# battery_controller.net
KiCad netlist of a schematic drawn in EAGLE
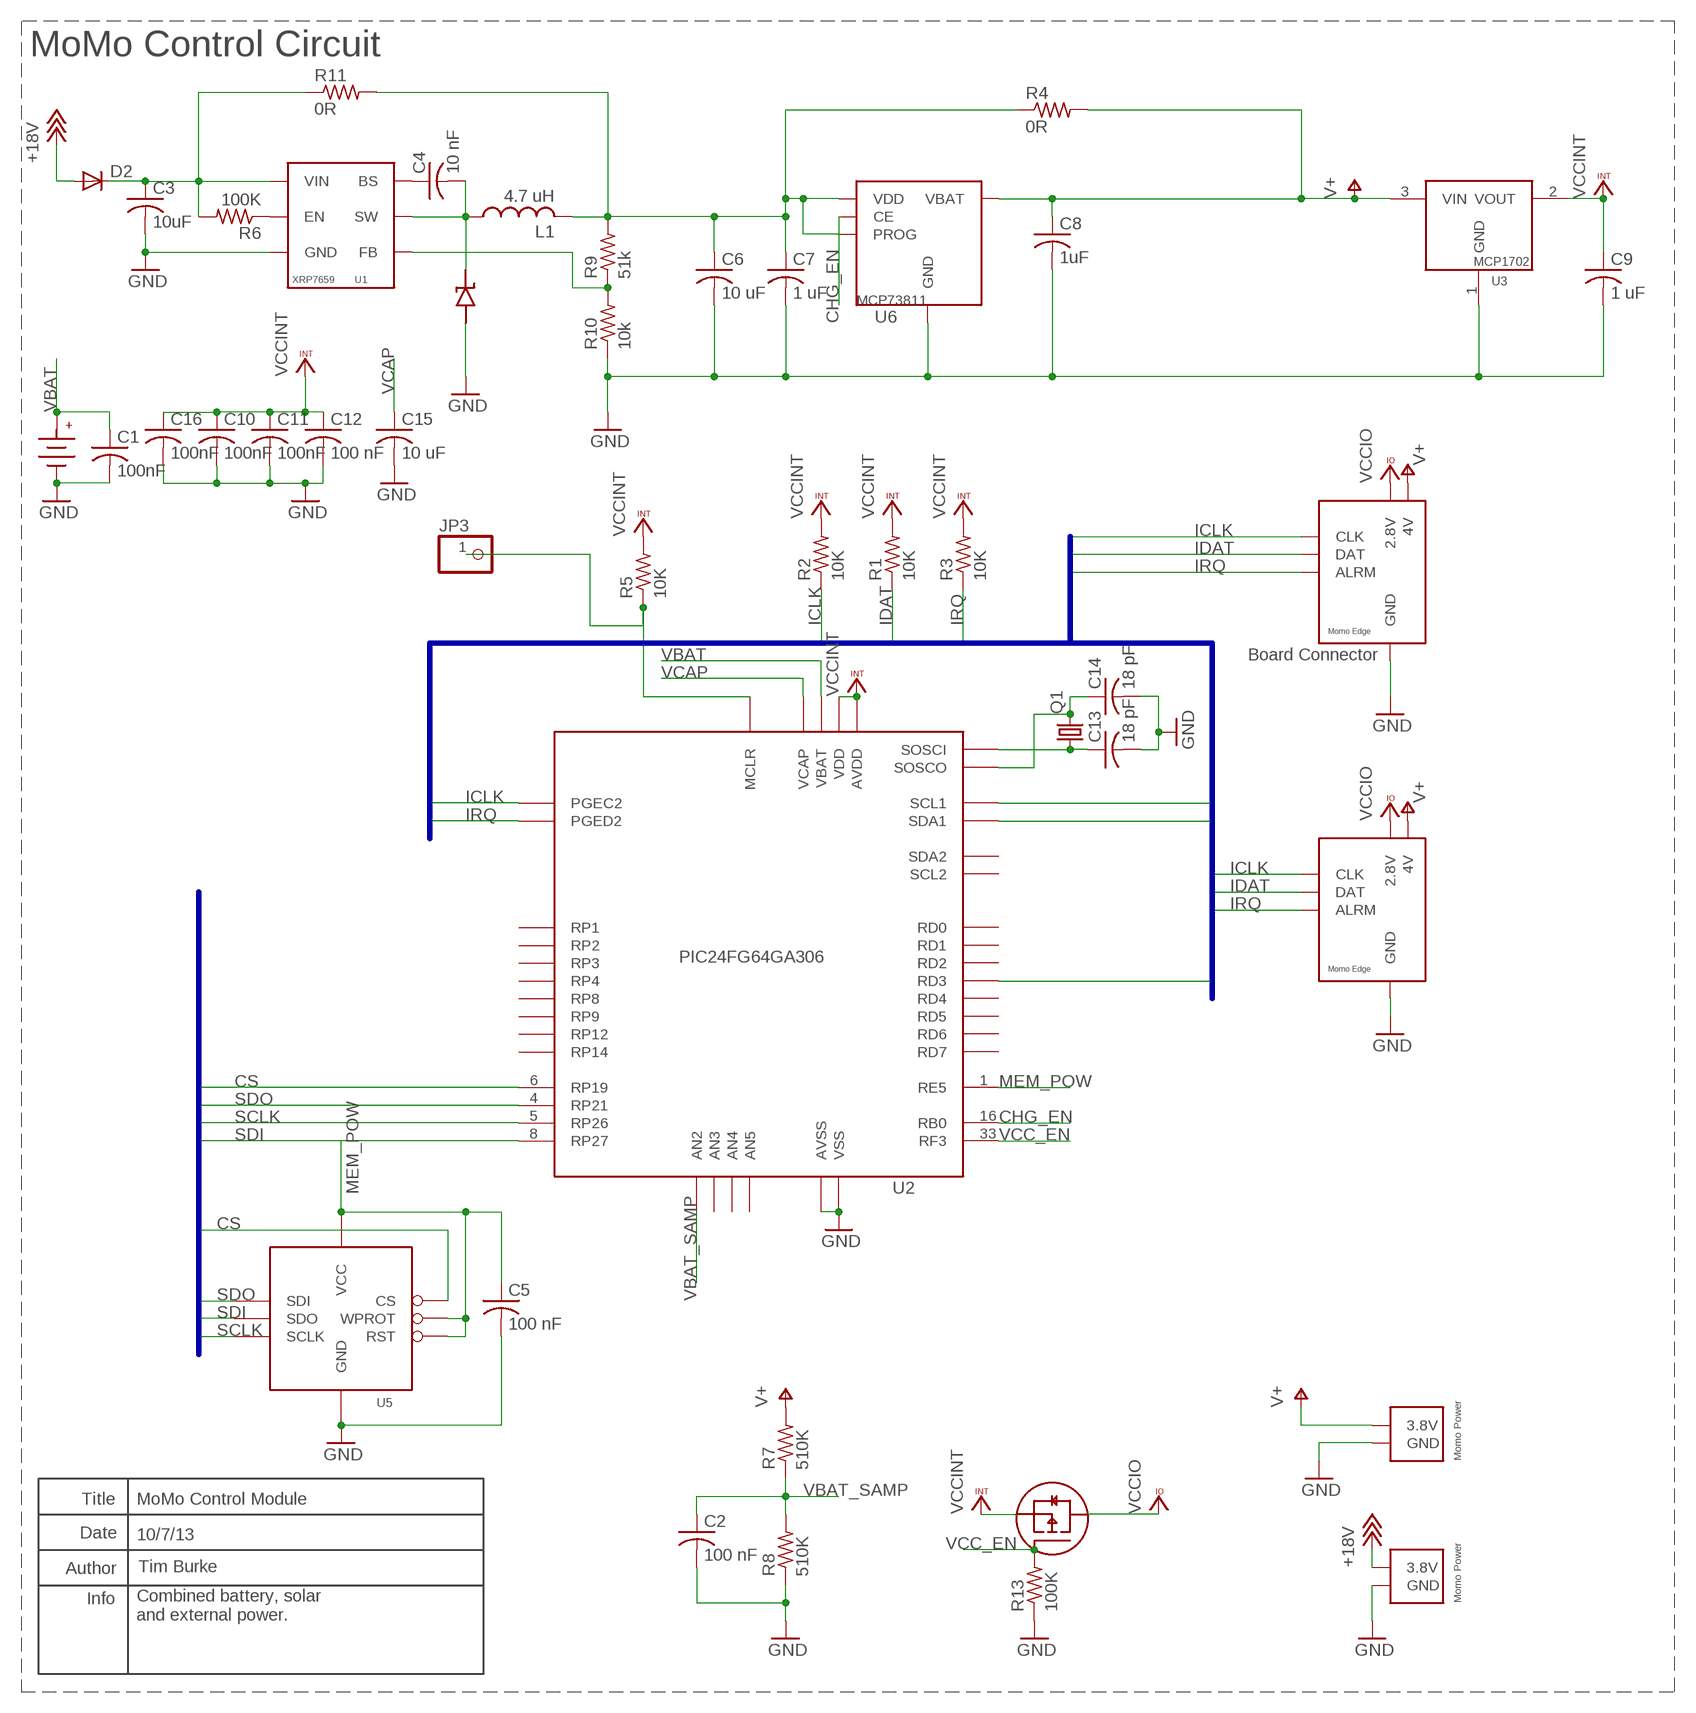
[diagram p0: schematic, sheet 1]

(export (version "E")
  (design (tool "Eeschema 10.0.6"))
  (components
    (comp (ref "BATT1")
      (value "CR1025-HOLDER")
      (footprint "eagle-import:CR1025-HOLDER")
      (libsource (lib "eagle-import") (part "CR1025-HOLDER"))
    )
    (comp (ref "C1")
      (value "100nF")
      (footprint "eagle-import:C0402")
      (libsource (lib "eagle-import") (part "C-USC0402"))
    )
    (comp (ref "C2")
      (value "100 nF")
      (footprint "eagle-import:C0402")
      (libsource (lib "eagle-import") (part "C-USC0402"))
    )
    (comp (ref "C3")
      (value "10uF")
      (footprint "eagle-import:C0805")
      (libsource (lib "eagle-import") (part "C-USC0805"))
    )
    (comp (ref "C4")
      (value "10 nF")
      (footprint "eagle-import:C0402")
      (libsource (lib "eagle-import") (part "C-USC0402"))
    )
    (comp (ref "C5")
      (value "100 nF")
      (footprint "eagle-import:C0402")
      (libsource (lib "eagle-import") (part "C-USC0402"))
    )
    (comp (ref "C6")
      (value "10 uF")
      (footprint "eagle-import:C0805")
      (libsource (lib "eagle-import") (part "C-USC0805"))
    )
    (comp (ref "C7")
      (value "1 uF")
      (footprint "eagle-import:C0402")
      (libsource (lib "eagle-import") (part "C-USC0402"))
    )
    (comp (ref "C8")
      (value "1uF")
      (footprint "eagle-import:C0402")
      (libsource (lib "eagle-import") (part "C-USC0402"))
    )
    (comp (ref "C9")
      (value "1 uF")
      (footprint "eagle-import:C0402")
      (libsource (lib "eagle-import") (part "C-USC0402"))
    )
    (comp (ref "C10")
      (value "100nF")
      (footprint "eagle-import:C0402")
      (libsource (lib "eagle-import") (part "C-USC0402"))
    )
    (comp (ref "C11")
      (value "100nF")
      (footprint "eagle-import:C0402")
      (libsource (lib "eagle-import") (part "C-USC0402"))
    )
    (comp (ref "C12")
      (value "100 nF")
      (footprint "eagle-import:C0402")
      (libsource (lib "eagle-import") (part "C-USC0402"))
    )
    (comp (ref "C13")
      (value "18 pF")
      (footprint "eagle-import:C0402K")
      (libsource (lib "eagle-import") (part "C-USC0402K"))
    )
    (comp (ref "C14")
      (value "18 pF")
      (footprint "eagle-import:C0402K")
      (libsource (lib "eagle-import") (part "C-USC0402K"))
    )
    (comp (ref "C15")
      (value "10 uF")
      (footprint "eagle-import:C0805")
      (libsource (lib "eagle-import") (part "C-USC0805"))
    )
    (comp (ref "C16")
      (value "100nF")
      (footprint "eagle-import:C0402")
      (libsource (lib "eagle-import") (part "C-USC0402"))
    )
    (comp (ref "D1")
      (value "DIODE_SS2P3SS2P3")
      (footprint "eagle-import:DIODE_SS2P3")
      (libsource (lib "eagle-import") (part "DIODE_SS2P3SS2P3"))
    )
    (comp (ref "D2")
      (value "DIODE-DO214AC")
      (footprint "eagle-import:DO214AC")
      (description "Schottky Diode")
      (libsource (lib "eagle-import") (part "DIODE-DO214AC"))
    )
    (comp (ref "JP1")
      (value "MOMO-VERT-6M")
      (footprint "eagle-import:1X06")
      (libsource (lib "eagle-import") (part "MOMO-VERT-6M"))
    )
    (comp (ref "JP2")
      (value "MOMO-EDGE-6F")
      (footprint "eagle-import:MOMO-EDGE-8F")
      (libsource (lib "eagle-import") (part "MOMO-EDGE-6F"))
    )
    (comp (ref "JP3")
      (value "PINHD-1X1")
      (footprint "eagle-import:1X01")
      (libsource (lib "eagle-import") (part "PINHD-1X1"))
    )
    (comp (ref "JP4")
      (value "MOMO-EDGE-POWER-M")
      (footprint "eagle-import:MOMO-EDGE-SMALL-2M")
      (fields (field (name "DIGIKEY-PN") "A19450-ND"))
      (libsource (lib "eagle-import") (part "MOMO-EDGE-POWER-M"))
    )
    (comp (ref "JP5")
      (value "MOMO-EDGE-POWER-M")
      (footprint "eagle-import:MOMO-EDGE-SMALL-2M")
      (fields (field (name "DIGIKEY-PN") "A19450-ND"))
      (libsource (lib "eagle-import") (part "MOMO-EDGE-POWER-M"))
    )
    (comp (ref "L1")
      (value "4.7 uH")
      (footprint "eagle-import:NR6028-INDUCTOR")
      (libsource (lib "eagle-import") (part "NR6028-INDUCTOR"))
    )
    (comp (ref "Q1")
      (value "CRYSTALTC26H")
      (footprint "eagle-import:TC26H")
      (libsource (lib "eagle-import") (part "CRYSTALTC26H"))
    )
    (comp (ref "Q2")
      (value "P-MOSFET")
      (footprint "eagle-import:SOT23")
      (libsource (lib "eagle-import") (part "P-MOSFET"))
    )
    (comp (ref "R1")
      (value "10K")
      (footprint "eagle-import:R0603")
      (libsource (lib "eagle-import") (part "R-US_R0603"))
    )
    (comp (ref "R2")
      (value "10K")
      (footprint "eagle-import:R0603")
      (libsource (lib "eagle-import") (part "R-US_R0603"))
    )
    (comp (ref "R3")
      (value "10K")
      (footprint "eagle-import:R0603")
      (libsource (lib "eagle-import") (part "R-US_R0603"))
    )
    (comp (ref "R4")
      (value "0R")
      (footprint "eagle-import:R0603")
      (libsource (lib "eagle-import") (part "R-US_R0603"))
    )
    (comp (ref "R5")
      (value "10K")
      (footprint "eagle-import:R0603")
      (libsource (lib "eagle-import") (part "R-US_R0603"))
    )
    (comp (ref "R6")
      (value "100K")
      (footprint "eagle-import:R0603")
      (libsource (lib "eagle-import") (part "R-US_R0603"))
    )
    (comp (ref "R7")
      (value "510K")
      (footprint "eagle-import:R0603")
      (libsource (lib "eagle-import") (part "R-US_R0603"))
    )
    (comp (ref "R8")
      (value "510K")
      (footprint "eagle-import:R0603")
      (libsource (lib "eagle-import") (part "R-US_R0603"))
    )
    (comp (ref "R9")
      (value "51k")
      (footprint "eagle-import:R0603")
      (libsource (lib "eagle-import") (part "R-US_R0603"))
    )
    (comp (ref "R10")
      (value "10k")
      (footprint "eagle-import:R0603")
      (libsource (lib "eagle-import") (part "R-US_R0603"))
    )
    (comp (ref "R11")
      (value "0R")
      (footprint "eagle-import:R0603")
      (libsource (lib "eagle-import") (part "R-US_R0603"))
    )
    (comp (ref "R13")
      (value "100K")
      (footprint "eagle-import:R0603")
      (libsource (lib "eagle-import") (part "R-US_R0603"))
    )
    (comp (ref "U1")
      (value "XRP7659")
      (footprint "eagle-import:SOT23-6L")
      (libsource (lib "eagle-import") (part "XRP7659"))
    )
    (comp (ref "U2")
      (value "PIC24FJ64GA306")
      (footprint "eagle-import:TQFP64-10X10")
      (libsource (lib "eagle-import") (part "PIC24FJ64GA306"))
    )
    (comp (ref "U3")
      (value "MCP1702")
      (footprint "eagle-import:SOT23")
      (libsource (lib "eagle-import") (part "MCP1702"))
    )
    (comp (ref "U5")
      (value "FLASH8MSOP8")
      (footprint "eagle-import:SOP08")
      (libsource (lib "eagle-import") (part "FLASH8MSOP8"))
    )
    (comp (ref "U6")
      (value "MCP73811")
      (footprint "eagle-import:SOT23-5L")
      (libsource (lib "eagle-import") (part "MCP73811"))
    )
  )
  (nets
    (net (code "1") (name "+18V") (class "Default")
      (node (ref "D2") (pin "A") (pinfunction "A_A") (pintype "passive"))
      (node (ref "JP5") (pin "2") (pinfunction "3.8V_2") (pintype "power_in"))
    )
    (net (code "2") (name "/CHG_EN") (class "Default")
      (node (ref "U2") (pin "16") (pinfunction "RB0_16") (pintype "bidirectional"))
      (node (ref "U6") (pin "1") (pinfunction "CE_1") (pintype "bidirectional"))
    )
    (net (code "3") (name "/CS") (class "Default")
      (node (ref "U2") (pin "6") (pinfunction "RP19_6") (pintype "bidirectional"))
      (node (ref "U5") (pin "1") (pinfunction "CS_1") (pintype "bidirectional"))
    )
    (net (code "4") (name "/ICLK") (class "Default")
      (node (ref "JP1") (pin "3") (pinfunction "CLK_3") (pintype "bidirectional"))
      (node (ref "JP2") (pin "CLK") (pinfunction "CLK_CLK") (pintype "bidirectional"))
      (node (ref "R2") (pin "1") (pinfunction "1_1") (pintype "passive"))
      (node (ref "U2") (pin "17") (pinfunction "PGEC2_17") (pintype "bidirectional"))
      (node (ref "U2") (pin "37") (pinfunction "SCL1_37") (pintype "bidirectional"))
    )
    (net (code "5") (name "/IDAT") (class "Default")
      (node (ref "JP1") (pin "4") (pinfunction "DAT_4") (pintype "bidirectional"))
      (node (ref "JP2") (pin "DAT") (pinfunction "DAT_DAT") (pintype "bidirectional"))
      (node (ref "R1") (pin "1") (pinfunction "1_1") (pintype "passive"))
      (node (ref "U2") (pin "36") (pinfunction "SDA1_36") (pintype "bidirectional"))
    )
    (net (code "6") (name "/IRQ") (class "Default")
      (node (ref "JP1") (pin "5") (pinfunction "ALRM_5") (pintype "bidirectional"))
      (node (ref "JP2") (pin "ARLM") (pinfunction "ALRM_ARLM") (pintype "bidirectional"))
      (node (ref "R3") (pin "1") (pinfunction "1_1") (pintype "passive"))
      (node (ref "U2") (pin "18") (pinfunction "PGED2_18") (pintype "bidirectional"))
      (node (ref "U2") (pin "51") (pinfunction "RD3_51") (pintype "bidirectional"))
    )
    (net (code "7") (name "/MEM_POW") (class "Default")
      (node (ref "C5") (pin "1") (pinfunction "1_1") (pintype "passive"))
      (node (ref "U2") (pin "1") (pinfunction "RE5_1") (pintype "bidirectional"))
      (node (ref "U5") (pin "3") (pinfunction "WPROT_3") (pintype "bidirectional"))
      (node (ref "U5") (pin "7") (pinfunction "RST_7") (pintype "bidirectional"))
      (node (ref "U5") (pin "8") (pinfunction "VCC_8") (pintype "power_in"))
    )
    (net (code "8") (name "/SCLK") (class "Default")
      (node (ref "U2") (pin "5") (pinfunction "RP26_5") (pintype "bidirectional"))
      (node (ref "U5") (pin "6") (pinfunction "SCLK_6") (pintype "bidirectional"))
    )
    (net (code "9") (name "/SDI") (class "Default")
      (node (ref "U2") (pin "8") (pinfunction "RP27_8") (pintype "bidirectional"))
      (node (ref "U5") (pin "2") (pinfunction "SDO_2") (pintype "bidirectional"))
    )
    (net (code "10") (name "/SDO") (class "Default")
      (node (ref "U2") (pin "4") (pinfunction "RP21_4") (pintype "bidirectional"))
      (node (ref "U5") (pin "5") (pinfunction "SDI_5") (pintype "bidirectional"))
    )
    (net (code "11") (name "/VBAT") (class "Default")
      (node (ref "BATT1") (pin "+") (pinfunction "+_+") (pintype "power_in"))
      (node (ref "C1") (pin "1") (pinfunction "1_1") (pintype "passive"))
      (node (ref "U2") (pin "57") (pinfunction "VBAT_57") (pintype "bidirectional"))
    )
    (net (code "12") (name "/VBAT_SAMP") (class "Default")
      (node (ref "C2") (pin "1") (pinfunction "1_1") (pintype "passive"))
      (node (ref "R7") (pin "1") (pinfunction "1_1") (pintype "passive"))
      (node (ref "R8") (pin "2") (pinfunction "2_2") (pintype "passive"))
      (node (ref "U2") (pin "14") (pinfunction "AN2_14") (pintype "bidirectional"))
    )
    (net (code "13") (name "/VCAP") (class "Default")
      (node (ref "C15") (pin "1") (pinfunction "1_1") (pintype "passive"))
      (node (ref "U2") (pin "56") (pinfunction "VCAP_56") (pintype "bidirectional"))
    )
    (net (code "14") (name "/VCC_EN") (class "Default")
      (node (ref "Q2") (pin "1") (pinfunction "GATE_1") (pintype "bidirectional"))
      (node (ref "R13") (pin "2") (pinfunction "2_2") (pintype "passive"))
      (node (ref "U2") (pin "33") (pinfunction "RF3_33") (pintype "bidirectional"))
    )
    (net (code "15") (name "GND") (class "Default")
      (node (ref "BATT1") (pin "-1") (pinfunction "-_-1") (pintype "power_in"))
      (node (ref "BATT1") (pin "-2") (pinfunction "-_-2") (pintype "power_in"))
      (node (ref "C1") (pin "2") (pinfunction "2_2") (pintype "passive"))
      (node (ref "C10") (pin "2") (pinfunction "2_2") (pintype "passive"))
      (node (ref "C11") (pin "2") (pinfunction "2_2") (pintype "passive"))
      (node (ref "C12") (pin "2") (pinfunction "2_2") (pintype "passive"))
      (node (ref "C13") (pin "2") (pinfunction "2_2") (pintype "passive"))
      (node (ref "C14") (pin "2") (pinfunction "2_2") (pintype "passive"))
      (node (ref "C15") (pin "2") (pinfunction "2_2") (pintype "passive"))
      (node (ref "C16") (pin "2") (pinfunction "2_2") (pintype "passive"))
      (node (ref "C2") (pin "2") (pinfunction "2_2") (pintype "passive"))
      (node (ref "C3") (pin "2") (pinfunction "2_2") (pintype "passive"))
      (node (ref "C5") (pin "2") (pinfunction "2_2") (pintype "passive"))
      (node (ref "C6") (pin "2") (pinfunction "2_2") (pintype "passive"))
      (node (ref "C7") (pin "2") (pinfunction "2_2") (pintype "passive"))
      (node (ref "C8") (pin "2") (pinfunction "2_2") (pintype "passive"))
      (node (ref "C9") (pin "2") (pinfunction "2_2") (pintype "passive"))
      (node (ref "D1") (pin "AN") (pinfunction "AN_AN") (pintype "bidirectional"))
      (node (ref "JP1") (pin "7") (pinfunction "GND_7") (pintype "power_in"))
      (node (ref "JP2") (pin "GND") (pinfunction "GND_GND") (pintype "power_in"))
      (node (ref "JP4") (pin "1") (pinfunction "GND_1") (pintype "power_in"))
      (node (ref "JP5") (pin "1") (pinfunction "GND_1") (pintype "power_in"))
      (node (ref "R10") (pin "1") (pinfunction "1_1") (pintype "passive"))
      (node (ref "R13") (pin "1") (pinfunction "1_1") (pintype "passive"))
      (node (ref "R8") (pin "1") (pinfunction "1_1") (pintype "passive"))
      (node (ref "U1") (pin "2") (pinfunction "GND_2") (pintype "bidirectional"))
      (node (ref "U2") (pin "20") (pinfunction "AVSS_20") (pintype "bidirectional"))
      (node (ref "U2") (pin "25") (pinfunction "VSS_25") (pintype "bidirectional"))
      (node (ref "U2") (pin "41") (pinfunction "VSS_41") (pintype "bidirectional"))
      (node (ref "U2") (pin "9") (pinfunction "VSS_9") (pintype "bidirectional"))
      (node (ref "U3") (pin "1") (pinfunction "GND_1") (pintype "bidirectional"))
      (node (ref "U5") (pin "4") (pinfunction "GND_4") (pintype "power_in"))
      (node (ref "U6") (pin "2") (pinfunction "GND_2") (pintype "bidirectional"))
    )
    (net (code "16") (name "Net-(U1-BS)") (class "Default")
      (node (ref "C4") (pin "1") (pinfunction "1_1") (pintype "passive"))
      (node (ref "U1") (pin "1") (pinfunction "BS_1") (pintype "bidirectional"))
    )
    (net (code "17") (name "Net-(U1-EN)") (class "Default")
      (node (ref "R6") (pin "1") (pinfunction "1_1") (pintype "passive"))
      (node (ref "U1") (pin "4") (pinfunction "EN_4") (pintype "bidirectional"))
    )
    (net (code "18") (name "Net-(U1-FB)") (class "Default")
      (node (ref "R10") (pin "2") (pinfunction "2_2") (pintype "passive"))
      (node (ref "R9") (pin "1") (pinfunction "1_1") (pintype "passive"))
      (node (ref "U1") (pin "3") (pinfunction "FB_3") (pintype "bidirectional"))
    )
    (net (code "19") (name "Net-(U1-SW)") (class "Default")
      (node (ref "C4") (pin "2") (pinfunction "2_2") (pintype "passive"))
      (node (ref "D1") (pin "CATH") (pinfunction "CATH_CATH") (pintype "bidirectional"))
      (node (ref "L1") (pin "1") (pinfunction "1_1") (pintype "passive"))
      (node (ref "U1") (pin "6") (pinfunction "SW_6") (pintype "bidirectional"))
    )
    (net (code "20") (name "Net-(U1-VIN)") (class "Default")
      (node (ref "C3") (pin "1") (pinfunction "1_1") (pintype "passive"))
      (node (ref "D2") (pin "C") (pinfunction "C_C") (pintype "passive"))
      (node (ref "R11") (pin "1") (pinfunction "1_1") (pintype "passive"))
      (node (ref "R6") (pin "2") (pinfunction "2_2") (pintype "passive"))
      (node (ref "U1") (pin "5") (pinfunction "VIN_5") (pintype "bidirectional"))
    )
    (net (code "21") (name "Net-(U2-MCLR)") (class "Default")
      (node (ref "JP3") (pin "1") (pinfunction "1_1") (pintype "passive"))
      (node (ref "R5") (pin "1") (pinfunction "1_1") (pintype "passive"))
      (node (ref "U2") (pin "7") (pinfunction "MCLR_7") (pintype "bidirectional"))
    )
    (net (code "22") (name "Net-(U2-SOSCI)") (class "Default")
      (node (ref "C13") (pin "1") (pinfunction "1_1") (pintype "passive"))
      (node (ref "Q1") (pin "1") (pinfunction "1_1") (pintype "passive"))
      (node (ref "U2") (pin "47") (pinfunction "SOSCI_47") (pintype "bidirectional"))
    )
    (net (code "23") (name "Net-(U2-SOSCO)") (class "Default")
      (node (ref "C14") (pin "1") (pinfunction "1_1") (pintype "passive"))
      (node (ref "Q1") (pin "2") (pinfunction "2_2") (pintype "passive"))
      (node (ref "U2") (pin "48") (pinfunction "SOSCO_48") (pintype "bidirectional"))
    )
    (net (code "24") (name "Net-(U6-PROG)") (class "Default")
      (node (ref "C6") (pin "1") (pinfunction "1_1") (pintype "passive"))
      (node (ref "C7") (pin "1") (pinfunction "1_1") (pintype "passive"))
      (node (ref "L1") (pin "2") (pinfunction "2_2") (pintype "passive"))
      (node (ref "R11") (pin "2") (pinfunction "2_2") (pintype "passive"))
      (node (ref "R4") (pin "1") (pinfunction "1_1") (pintype "passive"))
      (node (ref "R9") (pin "2") (pinfunction "2_2") (pintype "passive"))
      (node (ref "U6") (pin "4") (pinfunction "VDD_4") (pintype "bidirectional"))
      (node (ref "U6") (pin "5") (pinfunction "PROG_5") (pintype "bidirectional"))
    )
    (net (code "25") (name "V+") (class "Default")
      (node (ref "C8") (pin "1") (pinfunction "1_1") (pintype "passive"))
      (node (ref "JP1") (pin "6") (pinfunction "4V_6") (pintype "power_in"))
      (node (ref "JP2") (pin "V4") (pinfunction "4V_V4") (pintype "power_in"))
      (node (ref "JP4") (pin "2") (pinfunction "3.8V_2") (pintype "power_in"))
      (node (ref "R4") (pin "2") (pinfunction "2_2") (pintype "passive"))
      (node (ref "R7") (pin "2") (pinfunction "2_2") (pintype "passive"))
      (node (ref "U3") (pin "3") (pinfunction "VIN_3") (pintype "bidirectional"))
      (node (ref "U6") (pin "3") (pinfunction "VBAT_3") (pintype "bidirectional"))
    )
    (net (code "26") (name "VCCINT") (class "Default")
      (node (ref "C10") (pin "1") (pinfunction "1_1") (pintype "passive"))
      (node (ref "C11") (pin "1") (pinfunction "1_1") (pintype "passive"))
      (node (ref "C12") (pin "1") (pinfunction "1_1") (pintype "passive"))
      (node (ref "C16") (pin "1") (pinfunction "1_1") (pintype "passive"))
      (node (ref "C9") (pin "1") (pinfunction "1_1") (pintype "passive"))
      (node (ref "Q2") (pin "2") (pinfunction "SOURCE_2") (pintype "bidirectional"))
      (node (ref "R1") (pin "2") (pinfunction "2_2") (pintype "passive"))
      (node (ref "R2") (pin "2") (pinfunction "2_2") (pintype "passive"))
      (node (ref "R3") (pin "2") (pinfunction "2_2") (pintype "passive"))
      (node (ref "R5") (pin "2") (pinfunction "2_2") (pintype "passive"))
      (node (ref "U2") (pin "10") (pinfunction "VDD_10") (pintype "bidirectional"))
      (node (ref "U2") (pin "19") (pinfunction "AVDD_19") (pintype "bidirectional"))
      (node (ref "U2") (pin "26") (pinfunction "VDD_26") (pintype "bidirectional"))
      (node (ref "U2") (pin "38") (pinfunction "VDD_38") (pintype "bidirectional"))
      (node (ref "U3") (pin "2") (pinfunction "VOUT_2") (pintype "bidirectional"))
    )
    (net (code "27") (name "VCCIO") (class "Default")
      (node (ref "JP1") (pin "1") (pinfunction "2.8V_1") (pintype "power_in"))
      (node (ref "JP2") (pin "V28") (pinfunction "2.8V_V28") (pintype "power_in"))
      (node (ref "Q2") (pin "3") (pinfunction "DRAIN_3") (pintype "bidirectional"))
    )
    (net (code "28") (name "unconnected-(U2-AN3-Pad13)") (class "Default")
      (node (ref "U2") (pin "13") (pinfunction "AN3_13") (pintype "bidirectional"))
    )
    (net (code "29") (name "unconnected-(U2-AN4-Pad12)") (class "Default")
      (node (ref "U2") (pin "12") (pinfunction "AN4_12") (pintype "bidirectional"))
    )
    (net (code "30") (name "unconnected-(U2-AN5-Pad11)") (class "Default")
      (node (ref "U2") (pin "11") (pinfunction "AN5_11") (pintype "bidirectional"))
    )
    (net (code "31") (name "unconnected-(U2-RD0-Pad46)") (class "Default")
      (node (ref "U2") (pin "46") (pinfunction "RD0_46") (pintype "bidirectional"))
    )
    (net (code "32") (name "unconnected-(U2-RD1-Pad49)") (class "Default")
      (node (ref "U2") (pin "49") (pinfunction "RD1_49") (pintype "bidirectional"))
    )
    (net (code "33") (name "unconnected-(U2-RD2-Pad50)") (class "Default")
      (node (ref "U2") (pin "50") (pinfunction "RD2_50") (pintype "bidirectional"))
    )
    (net (code "34") (name "unconnected-(U2-RD4-Pad52)") (class "Default")
      (node (ref "U2") (pin "52") (pinfunction "RD4_52") (pintype "bidirectional"))
    )
    (net (code "35") (name "unconnected-(U2-RD5-Pad53)") (class "Default")
      (node (ref "U2") (pin "53") (pinfunction "RD5_53") (pintype "bidirectional"))
    )
    (net (code "36") (name "unconnected-(U2-RD6-Pad54)") (class "Default")
      (node (ref "U2") (pin "54") (pinfunction "RD6_54") (pintype "bidirectional"))
    )
    (net (code "37") (name "unconnected-(U2-RD7-Pad55)") (class "Default")
      (node (ref "U2") (pin "55") (pinfunction "RD7_55") (pintype "bidirectional"))
    )
    (net (code "38") (name "unconnected-(U2-RP1-Pad15)") (class "Default")
      (node (ref "U2") (pin "15") (pinfunction "RP1_15") (pintype "bidirectional"))
    )
    (net (code "39") (name "unconnected-(U2-RP2-Pad42)") (class "Default")
      (node (ref "U2") (pin "42") (pinfunction "RP2_42") (pintype "bidirectional"))
    )
    (net (code "40") (name "unconnected-(U2-RP3-Pad44)") (class "Default")
      (node (ref "U2") (pin "44") (pinfunction "RP3_44") (pintype "bidirectional"))
    )
    (net (code "41") (name "unconnected-(U2-RP4-Pad43)") (class "Default")
      (node (ref "U2") (pin "43") (pinfunction "RP4_43") (pintype "bidirectional"))
    )
    (net (code "42") (name "unconnected-(U2-RP8-Pad21)") (class "Default")
      (node (ref "U2") (pin "21") (pinfunction "RP8_21") (pintype "bidirectional"))
    )
    (net (code "43") (name "unconnected-(U2-RP9-Pad22)") (class "Default")
      (node (ref "U2") (pin "22") (pinfunction "RP9_22") (pintype "bidirectional"))
    )
    (net (code "44") (name "unconnected-(U2-RP12-Pad45)") (class "Default")
      (node (ref "U2") (pin "45") (pinfunction "RP12_45") (pintype "bidirectional"))
    )
    (net (code "45") (name "unconnected-(U2-RP14-Pad29)") (class "Default")
      (node (ref "U2") (pin "29") (pinfunction "RP14_29") (pintype "bidirectional"))
    )
    (net (code "46") (name "unconnected-(U2-SCL2-Pad32)") (class "Default")
      (node (ref "U2") (pin "32") (pinfunction "SCL2_32") (pintype "bidirectional"))
    )
    (net (code "47") (name "unconnected-(U2-SDA2-Pad31)") (class "Default")
      (node (ref "U2") (pin "31") (pinfunction "SDA2_31") (pintype "bidirectional"))
    )
  )
)
